# pic_board.net
KiCad netlist of a schematic drawn in EAGLE
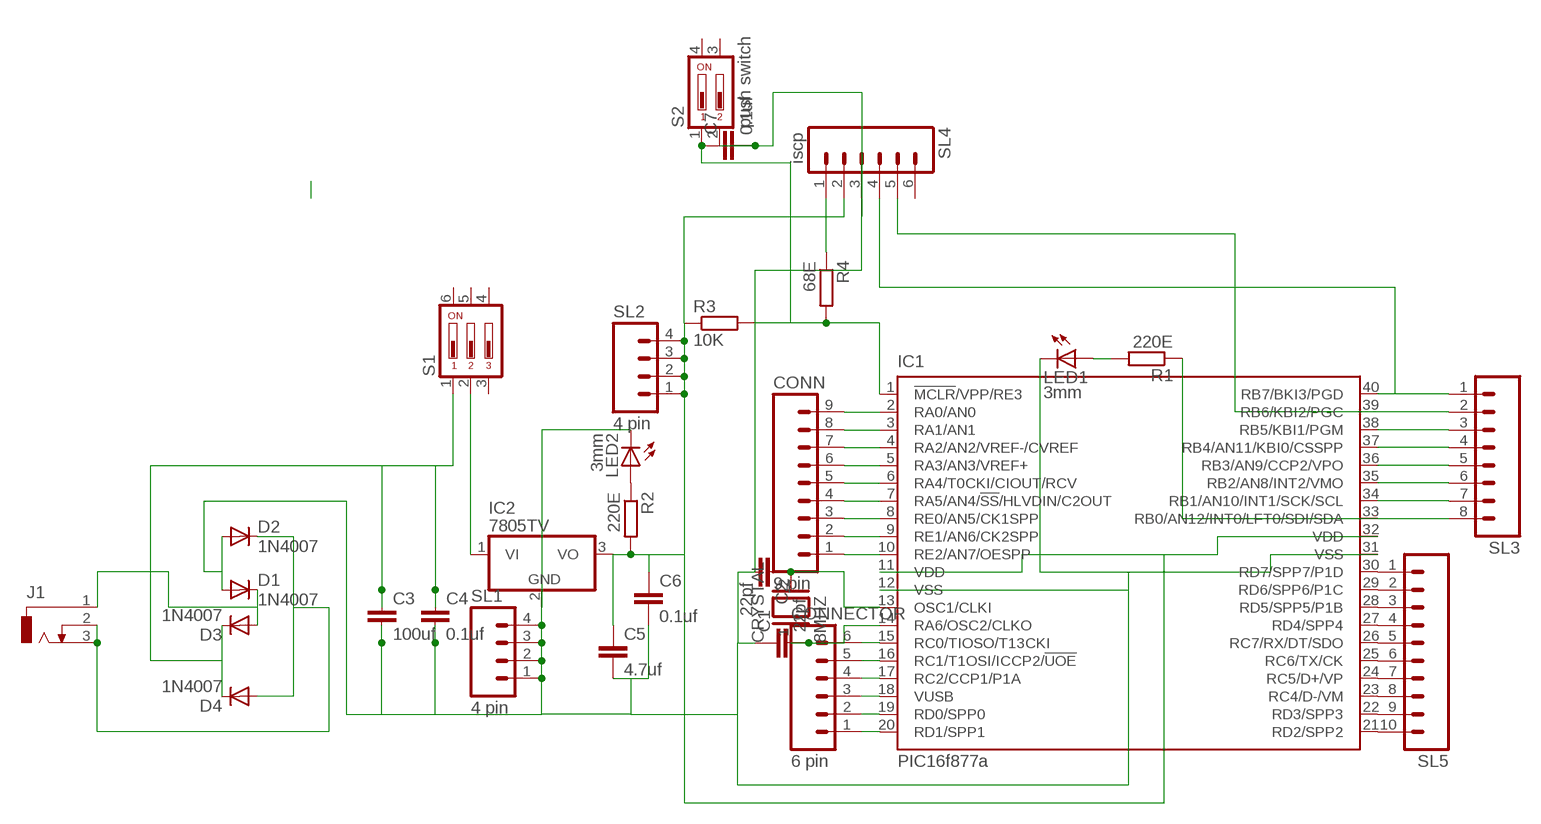
[diagram p0: schematic, sheet 1]

(export (version "E")
  (design (tool "Eeschema 10.0.6"))
  (components
    (comp (ref "C1")
      (value "22pf")
      (footprint "eagle-import:C2.5-2")
      (libsource (lib "eagle-import") (part "C2.5/2"))
    )
    (comp (ref "C2")
      (value "22pf")
      (footprint "eagle-import:C2.5-2")
      (libsource (lib "eagle-import") (part "C2.5/2"))
    )
    (comp (ref "C3")
      (value "100uf")
      (footprint "eagle-import:C5B7.2")
      (libsource (lib "eagle-import") (part "C5/7.2"))
    )
    (comp (ref "C4")
      (value "0.1uf")
      (footprint "eagle-import:C2.5-3")
      (libsource (lib "eagle-import") (part "C2,5-3"))
    )
    (comp (ref "C5")
      (value "4.7uf")
      (footprint "eagle-import:C5B7.2")
      (libsource (lib "eagle-import") (part "C5/7.2"))
    )
    (comp (ref "C6")
      (value "0.1uf")
      (footprint "eagle-import:C2.5-2")
      (libsource (lib "eagle-import") (part "C2.5/2"))
    )
    (comp (ref "C7")
      (value "0.1uf")
      (footprint "eagle-import:C2.5-3")
      (libsource (lib "eagle-import") (part "C2,5-3"))
    )
    (comp (ref "CONN")
      (value "9 pin")
      (footprint "eagle-import:09P")
      (libsource (lib "eagle-import") (part "M09"))
    )
    (comp (ref "CONNECTOR")
      (value "6 pin")
      (footprint "eagle-import:06P")
      (libsource (lib "eagle-import") (part "M06"))
    )
    (comp (ref "CRYSTAL")
      (value "8MHZ")
      (footprint "eagle-import:QS")
      (libsource (lib "eagle-import") (part "XTAL/S"))
    )
    (comp (ref "D1")
      (value "1N4007")
      (footprint "eagle-import:DO41-10")
      (libsource (lib "eagle-import") (part "1N4004"))
    )
    (comp (ref "D2")
      (value "1N4007")
      (footprint "eagle-import:DO41-10")
      (libsource (lib "eagle-import") (part "1N4004"))
    )
    (comp (ref "D3")
      (value "1N4007")
      (footprint "eagle-import:DO41-10")
      (libsource (lib "eagle-import") (part "1N4004"))
    )
    (comp (ref "D4")
      (value "1N4007")
      (footprint "eagle-import:DO41-10")
      (libsource (lib "eagle-import") (part "1N4004"))
    )
    (comp (ref "IC1")
      (value "PIC16f877a")
      (footprint "eagle-import:DIL40")
      (fields (field (name "MF") "MICROCHIP") (field (name "MPN") "PIC18F4455-I/P"))
      (libsource (lib "eagle-import") (part "PIC18F4_40455"))
    )
    (comp (ref "IC2")
      (value "7805TV")
      (footprint "eagle-import:TO220V")
      (libsource (lib "eagle-import") (part "78TV05"))
    )
    (comp (ref "J1")
      (value "DCJ0303")
      (footprint "eagle-import:DCJ0303")
      (libsource (lib "eagle-import") (part "DCJ0303"))
    )
    (comp (ref "LED1")
      (value "3mm")
      (footprint "eagle-import:LED3MM")
      (libsource (lib "eagle-import") (part "LED3MM"))
    )
    (comp (ref "LED2")
      (value "3mm")
      (footprint "eagle-import:LED3MM")
      (libsource (lib "eagle-import") (part "LED3MM"))
    )
    (comp (ref "R1")
      (value "220E")
      (footprint "eagle-import:0204_7")
      (libsource (lib "eagle-import") (part "R-EU_0204/7"))
    )
    (comp (ref "R2")
      (value "220E")
      (footprint "eagle-import:0204_7")
      (libsource (lib "eagle-import") (part "R-EU_0204/7"))
    )
    (comp (ref "R3")
      (value "10K")
      (footprint "eagle-import:0204_7")
      (libsource (lib "eagle-import") (part "R-EU_0204/7"))
    )
    (comp (ref "R4")
      (value "68E")
      (footprint "eagle-import:0204_7")
      (libsource (lib "eagle-import") (part "R-EU_0204/7"))
    )
    (comp (ref "S1")
      (value "DA03")
      (footprint "eagle-import:DA-03")
      (fields (field (name "MPN") "MCDA03"))
      (libsource (lib "eagle-import") (part "DA03"))
    )
    (comp (ref "S2")
      (value "push switch")
      (footprint "eagle-import:DP-02")
      (fields (field (name "MPN") "MCDP02"))
      (libsource (lib "eagle-import") (part "DP02"))
    )
    (comp (ref "SL1")
      (value "4 pin")
      (footprint "eagle-import:04P")
      (libsource (lib "eagle-import") (part "M04"))
    )
    (comp (ref "SL2")
      (value "4 pin")
      (footprint "eagle-import:04P")
      (libsource (lib "eagle-import") (part "M04"))
    )
    (comp (ref "SL3")
      (value "M08")
      (footprint "eagle-import:08P")
      (libsource (lib "eagle-import") (part "M08"))
    )
    (comp (ref "SL4")
      (value "iscp")
      (footprint "eagle-import:06P")
      (libsource (lib "eagle-import") (part "M06"))
    )
    (comp (ref "SL5")
      (value "M10")
      (footprint "eagle-import:10P")
      (libsource (lib "eagle-import") (part "M10"))
    )
  )
  (nets
    (net (code "1") (name "Net-(C3-Pad1)") (class "Default")
      (node (ref "C3") (pin "1") (pinfunction "1_1") (pintype "passive"))
      (node (ref "C4") (pin "1") (pinfunction "1_1") (pintype "passive"))
      (node (ref "D3") (pin "C") (pinfunction "C_C") (pintype "passive"))
      (node (ref "D4") (pin "C") (pinfunction "C_C") (pintype "passive"))
      (node (ref "S1") (pin "1") (pinfunction "1_1") (pintype "passive"))
    )
    (net (code "2") (name "Net-(D1-PadC)") (class "Default")
      (node (ref "D1") (pin "C") (pinfunction "C_C") (pintype "passive"))
      (node (ref "D3") (pin "A") (pinfunction "A_A") (pintype "passive"))
      (node (ref "J1") (pin "1") (pinfunction "1_1") (pintype "passive"))
    )
    (net (code "3") (name "Net-(D2-PadC)") (class "Default")
      (node (ref "D2") (pin "C") (pinfunction "C_C") (pintype "passive"))
      (node (ref "D4") (pin "A") (pinfunction "A_A") (pintype "passive"))
      (node (ref "J1") (pin "2") (pinfunction "2_2") (pintype "passive"))
      (node (ref "J1") (pin "3") (pinfunction "3_3") (pintype "passive"))
    )
    (net (code "4") (name "Net-(IC1-OSC1{slash}CLKI)") (class "Default")
      (node (ref "C2") (pin "1") (pinfunction "1_1") (pintype "passive"))
      (node (ref "CRYSTAL") (pin "2") (pinfunction "2_2") (pintype "passive"))
      (node (ref "IC1") (pin "13") (pinfunction "OSC1/CLKI_13") (pintype "input"))
    )
    (net (code "5") (name "Net-(IC1-RA0{slash}AN0)") (class "Default")
      (node (ref "CONN") (pin "9") (pinfunction "9_9") (pintype "passive"))
      (node (ref "IC1") (pin "2") (pinfunction "RA0/AN0_2") (pintype "bidirectional"))
    )
    (net (code "6") (name "Net-(IC1-RA1{slash}AN1)") (class "Default")
      (node (ref "CONN") (pin "8") (pinfunction "8_8") (pintype "passive"))
      (node (ref "IC1") (pin "3") (pinfunction "RA1/AN1_3") (pintype "bidirectional"))
    )
    (net (code "7") (name "Net-(IC1-RA2{slash}AN2{slash}VREF-{slash}CVREF)") (class "Default")
      (node (ref "CONN") (pin "7") (pinfunction "7_7") (pintype "passive"))
      (node (ref "IC1") (pin "4") (pinfunction "RA2/AN2/VREF-/CVREF_4") (pintype "bidirectional"))
    )
    (net (code "8") (name "Net-(IC1-RA3{slash}AN3{slash}VREF+)") (class "Default")
      (node (ref "CONN") (pin "6") (pinfunction "6_6") (pintype "passive"))
      (node (ref "IC1") (pin "5") (pinfunction "RA3/AN3/VREF+_5") (pintype "bidirectional"))
    )
    (net (code "9") (name "Net-(IC1-RA4{slash}T0CKI{slash}CIOUT{slash}RCV)") (class "Default")
      (node (ref "CONN") (pin "5") (pinfunction "5_5") (pintype "passive"))
      (node (ref "IC1") (pin "6") (pinfunction "RA4/T0CKI/CIOUT/RCV_6") (pintype "bidirectional"))
    )
    (net (code "10") (name "Net-(IC1-RA5{slash}AN4{slash}~{SS}{slash}HLVDIN{slash}C2OUT)") (class "Default")
      (node (ref "CONN") (pin "4") (pinfunction "4_4") (pintype "passive"))
      (node (ref "IC1") (pin "7") (pinfunction "RA5/AN4/~{SS}/HLVDIN/C2OUT_7") (pintype "bidirectional"))
    )
    (net (code "11") (name "Net-(IC1-RA6{slash}OSC2{slash}CLKO)") (class "Default")
      (node (ref "C1") (pin "2") (pinfunction "2_2") (pintype "passive"))
      (node (ref "CRYSTAL") (pin "1") (pinfunction "1_1") (pintype "passive"))
      (node (ref "IC1") (pin "14") (pinfunction "RA6/OSC2/CLKO_14") (pintype "output"))
    )
    (net (code "12") (name "Net-(IC1-RB0{slash}AN12{slash}INT0{slash}LFT0{slash}SDI{slash}SDA)") (class "Default")
      (node (ref "IC1") (pin "33") (pinfunction "RB0/AN12/INT0/LFT0/SDI/SDA_33") (pintype "bidirectional"))
      (node (ref "R1") (pin "1") (pinfunction "1_1") (pintype "passive"))
      (node (ref "SL3") (pin "8") (pinfunction "8_8") (pintype "passive"))
    )
    (net (code "13") (name "Net-(IC1-RB1{slash}AN10{slash}INT1{slash}SCK{slash}SCL)") (class "Default")
      (node (ref "IC1") (pin "34") (pinfunction "RB1/AN10/INT1/SCK/SCL_34") (pintype "bidirectional"))
      (node (ref "SL3") (pin "7") (pinfunction "7_7") (pintype "passive"))
    )
    (net (code "14") (name "Net-(IC1-RB2{slash}AN8{slash}INT2{slash}VMO)") (class "Default")
      (node (ref "IC1") (pin "35") (pinfunction "RB2/AN8/INT2/VMO_35") (pintype "bidirectional"))
      (node (ref "SL3") (pin "6") (pinfunction "6_6") (pintype "passive"))
    )
    (net (code "15") (name "Net-(IC1-RB3{slash}AN9{slash}CCP2{slash}VPO)") (class "Default")
      (node (ref "IC1") (pin "36") (pinfunction "RB3/AN9/CCP2/VPO_36") (pintype "bidirectional"))
      (node (ref "SL3") (pin "5") (pinfunction "5_5") (pintype "passive"))
    )
    (net (code "16") (name "Net-(IC1-RB4{slash}AN11{slash}KBI0{slash}CSSPP)") (class "Default")
      (node (ref "IC1") (pin "37") (pinfunction "RB4/AN11/KBI0/CSSPP_37") (pintype "bidirectional"))
      (node (ref "SL3") (pin "4") (pinfunction "4_4") (pintype "passive"))
    )
    (net (code "17") (name "Net-(IC1-RB5{slash}KBI1{slash}PGM)") (class "Default")
      (node (ref "IC1") (pin "38") (pinfunction "RB5/KBI1/PGM_38") (pintype "bidirectional"))
      (node (ref "SL3") (pin "3") (pinfunction "3_3") (pintype "passive"))
    )
    (net (code "18") (name "Net-(IC1-RB6{slash}KBI2{slash}PGC)") (class "Default")
      (node (ref "IC1") (pin "39") (pinfunction "RB6/KBI2/PGC_39") (pintype "bidirectional"))
      (node (ref "SL3") (pin "2") (pinfunction "2_2") (pintype "passive"))
      (node (ref "SL4") (pin "5") (pinfunction "5_5") (pintype "passive"))
    )
    (net (code "19") (name "Net-(IC1-RB7{slash}BKI3{slash}PGD)") (class "Default")
      (node (ref "IC1") (pin "40") (pinfunction "RB7/BKI3/PGD_40") (pintype "bidirectional"))
      (node (ref "SL3") (pin "1") (pinfunction "1_1") (pintype "passive"))
      (node (ref "SL4") (pin "4") (pinfunction "4_4") (pintype "passive"))
    )
    (net (code "20") (name "Net-(IC1-RC0{slash}TIOSO{slash}T13CKI)") (class "Default")
      (node (ref "CONNECTOR") (pin "6") (pinfunction "6_6") (pintype "passive"))
      (node (ref "IC1") (pin "15") (pinfunction "RC0/TIOSO/T13CKI_15") (pintype "bidirectional"))
    )
    (net (code "21") (name "Net-(IC1-RC1{slash}T1OSI{slash}ICCP2{slash}~{UOE})") (class "Default")
      (node (ref "CONNECTOR") (pin "5") (pinfunction "5_5") (pintype "passive"))
      (node (ref "IC1") (pin "16") (pinfunction "RC1/T1OSI/ICCP2/~{UOE}_16") (pintype "bidirectional"))
    )
    (net (code "22") (name "Net-(IC1-RC2{slash}CCP1{slash}P1A)") (class "Default")
      (node (ref "CONNECTOR") (pin "4") (pinfunction "4_4") (pintype "passive"))
      (node (ref "IC1") (pin "17") (pinfunction "RC2/CCP1/P1A_17") (pintype "bidirectional"))
    )
    (net (code "23") (name "Net-(IC1-RC4{slash}D-{slash}VM)") (class "Default")
      (node (ref "IC1") (pin "23") (pinfunction "RC4/D-/VM_23") (pintype "bidirectional"))
      (node (ref "SL5") (pin "8") (pinfunction "8_8") (pintype "passive"))
    )
    (net (code "24") (name "Net-(IC1-RC5{slash}D+{slash}VP)") (class "Default")
      (node (ref "IC1") (pin "24") (pinfunction "RC5/D+/VP_24") (pintype "bidirectional"))
      (node (ref "SL5") (pin "7") (pinfunction "7_7") (pintype "passive"))
    )
    (net (code "25") (name "Net-(IC1-RC6{slash}TX{slash}CK)") (class "Default")
      (node (ref "IC1") (pin "25") (pinfunction "RC6/TX/CK_25") (pintype "bidirectional"))
      (node (ref "SL5") (pin "6") (pinfunction "6_6") (pintype "passive"))
    )
    (net (code "26") (name "Net-(IC1-RC7{slash}RX{slash}DT{slash}SDO)") (class "Default")
      (node (ref "IC1") (pin "26") (pinfunction "RC7/RX/DT/SDO_26") (pintype "bidirectional"))
      (node (ref "SL5") (pin "5") (pinfunction "5_5") (pintype "passive"))
    )
    (net (code "27") (name "Net-(IC1-RD0{slash}SPP0)") (class "Default")
      (node (ref "CONNECTOR") (pin "2") (pinfunction "2_2") (pintype "passive"))
      (node (ref "IC1") (pin "19") (pinfunction "RD0/SPP0_19") (pintype "bidirectional"))
    )
    (net (code "28") (name "Net-(IC1-RD1{slash}SPP1)") (class "Default")
      (node (ref "CONNECTOR") (pin "1") (pinfunction "1_1") (pintype "passive"))
      (node (ref "IC1") (pin "20") (pinfunction "RD1/SPP1_20") (pintype "bidirectional"))
    )
    (net (code "29") (name "Net-(IC1-RD2{slash}SPP2)") (class "Default")
      (node (ref "IC1") (pin "21") (pinfunction "RD2/SPP2_21") (pintype "bidirectional"))
      (node (ref "SL5") (pin "10") (pinfunction "10_10") (pintype "passive"))
    )
    (net (code "30") (name "Net-(IC1-RD3{slash}SPP3)") (class "Default")
      (node (ref "IC1") (pin "22") (pinfunction "RD3/SPP3_22") (pintype "bidirectional"))
      (node (ref "SL5") (pin "9") (pinfunction "9_9") (pintype "passive"))
    )
    (net (code "31") (name "Net-(IC1-RD4{slash}SPP4)") (class "Default")
      (node (ref "IC1") (pin "27") (pinfunction "RD4/SPP4_27") (pintype "bidirectional"))
      (node (ref "SL5") (pin "4") (pinfunction "4_4") (pintype "passive"))
    )
    (net (code "32") (name "Net-(IC1-RD5{slash}SPP5{slash}P1B)") (class "Default")
      (node (ref "IC1") (pin "28") (pinfunction "RD5/SPP5/P1B_28") (pintype "bidirectional"))
      (node (ref "SL5") (pin "3") (pinfunction "3_3") (pintype "passive"))
    )
    (net (code "33") (name "Net-(IC1-RD6{slash}SPP6{slash}P1C)") (class "Default")
      (node (ref "IC1") (pin "29") (pinfunction "RD6/SPP6/P1C_29") (pintype "bidirectional"))
      (node (ref "SL5") (pin "2") (pinfunction "2_2") (pintype "passive"))
    )
    (net (code "34") (name "Net-(IC1-RD7{slash}SPP7{slash}P1D)") (class "Default")
      (node (ref "IC1") (pin "30") (pinfunction "RD7/SPP7/P1D_30") (pintype "bidirectional"))
      (node (ref "SL5") (pin "1") (pinfunction "1_1") (pintype "passive"))
    )
    (net (code "35") (name "Net-(IC1-RE0{slash}AN5{slash}CK1SPP)") (class "Default")
      (node (ref "CONN") (pin "3") (pinfunction "3_3") (pintype "passive"))
      (node (ref "IC1") (pin "8") (pinfunction "RE0/AN5/CK1SPP_8") (pintype "bidirectional"))
    )
    (net (code "36") (name "Net-(IC1-RE1{slash}AN6{slash}CK2SPP)") (class "Default")
      (node (ref "CONN") (pin "2") (pinfunction "2_2") (pintype "passive"))
      (node (ref "IC1") (pin "9") (pinfunction "RE1/AN6/CK2SPP_9") (pintype "bidirectional"))
    )
    (net (code "37") (name "Net-(IC1-RE2{slash}AN7{slash}OESPP)") (class "Default")
      (node (ref "CONN") (pin "1") (pinfunction "1_1") (pintype "passive"))
      (node (ref "IC1") (pin "10") (pinfunction "RE2/AN7/OESPP_10") (pintype "bidirectional"))
    )
    (net (code "38") (name "Net-(IC1-VUSB)") (class "Default")
      (node (ref "CONNECTOR") (pin "3") (pinfunction "3_3") (pintype "passive"))
      (node (ref "IC1") (pin "18") (pinfunction "VUSB_18") (pintype "bidirectional"))
    )
    (net (code "39") (name "Net-(IC1-~{MCLR}{slash}VPP{slash}RE3)") (class "Default")
      (node (ref "C7") (pin "1") (pinfunction "1_1") (pintype "passive"))
      (node (ref "IC1") (pin "1") (pinfunction "~{MCLR}/VPP/RE3_1") (pintype "input"))
      (node (ref "R3") (pin "2") (pinfunction "2_2") (pintype "passive"))
      (node (ref "R4") (pin "2") (pinfunction "2_2") (pintype "passive"))
      (node (ref "S2") (pin "1") (pinfunction "1_1") (pintype "passive"))
    )
    (net (code "40") (name "Net-(IC2-GND)") (class "Default")
      (node (ref "C1") (pin "1") (pinfunction "1_1") (pintype "passive"))
      (node (ref "C2") (pin "2") (pinfunction "2_2") (pintype "passive"))
      (node (ref "C3") (pin "2") (pinfunction "2_2") (pintype "passive"))
      (node (ref "C4") (pin "2") (pinfunction "2_2") (pintype "passive"))
      (node (ref "C5") (pin "2") (pinfunction "2_2") (pintype "passive"))
      (node (ref "C6") (pin "2") (pinfunction "2_2") (pintype "passive"))
      (node (ref "C7") (pin "2") (pinfunction "2_2") (pintype "passive"))
      (node (ref "D1") (pin "A") (pinfunction "A_A") (pintype "passive"))
      (node (ref "D2") (pin "A") (pinfunction "A_A") (pintype "passive"))
      (node (ref "IC1") (pin "12") (pinfunction "VSS_12") (pintype "power_in"))
      (node (ref "IC1") (pin "31") (pinfunction "VSS_31") (pintype "power_in"))
      (node (ref "IC2") (pin "2") (pinfunction "GND_2") (pintype "passive"))
      (node (ref "LED1") (pin "K") (pinfunction "C_K") (pintype "passive"))
      (node (ref "LED2") (pin "K") (pinfunction "C_K") (pintype "passive"))
      (node (ref "S2") (pin "2") (pinfunction "2_2") (pintype "passive"))
      (node (ref "SL1") (pin "1") (pinfunction "1_1") (pintype "passive"))
      (node (ref "SL1") (pin "2") (pinfunction "2_2") (pintype "passive"))
      (node (ref "SL1") (pin "3") (pinfunction "3_3") (pintype "passive"))
      (node (ref "SL1") (pin "4") (pinfunction "4_4") (pintype "passive"))
      (node (ref "SL4") (pin "3") (pinfunction "3_3") (pintype "passive"))
    )
    (net (code "41") (name "Net-(IC2-VI)") (class "Default")
      (node (ref "IC2") (pin "1") (pinfunction "VI_1") (pintype "input"))
      (node (ref "S1") (pin "2") (pinfunction "2_2") (pintype "passive"))
    )
    (net (code "42") (name "Net-(IC2-VO)") (class "Default")
      (node (ref "C5") (pin "1") (pinfunction "1_1") (pintype "passive"))
      (node (ref "C6") (pin "1") (pinfunction "1_1") (pintype "passive"))
      (node (ref "IC1") (pin "11") (pinfunction "VDD_11") (pintype "power_in"))
      (node (ref "IC1") (pin "32") (pinfunction "VDD_32") (pintype "power_in"))
      (node (ref "IC2") (pin "3") (pinfunction "VO_3") (pintype "passive"))
      (node (ref "R2") (pin "2") (pinfunction "2_2") (pintype "passive"))
      (node (ref "R3") (pin "1") (pinfunction "1_1") (pintype "passive"))
      (node (ref "SL2") (pin "1") (pinfunction "1_1") (pintype "passive"))
      (node (ref "SL2") (pin "2") (pinfunction "2_2") (pintype "passive"))
      (node (ref "SL2") (pin "3") (pinfunction "3_3") (pintype "passive"))
      (node (ref "SL2") (pin "4") (pinfunction "4_4") (pintype "passive"))
      (node (ref "SL4") (pin "2") (pinfunction "2_2") (pintype "passive"))
    )
    (net (code "43") (name "Net-(LED1-PadA)") (class "Default")
      (node (ref "LED1") (pin "A") (pinfunction "A_A") (pintype "passive"))
      (node (ref "R1") (pin "2") (pinfunction "2_2") (pintype "passive"))
    )
    (net (code "44") (name "Net-(LED2-PadA)") (class "Default")
      (node (ref "LED2") (pin "A") (pinfunction "A_A") (pintype "passive"))
      (node (ref "R2") (pin "1") (pinfunction "1_1") (pintype "passive"))
    )
    (net (code "45") (name "Net-(R4-Pad1)") (class "Default")
      (node (ref "R4") (pin "1") (pinfunction "1_1") (pintype "passive"))
      (node (ref "SL4") (pin "1") (pinfunction "1_1") (pintype "passive"))
    )
    (net (code "46") (name "unconnected-(S1-Pad3)") (class "Default")
      (node (ref "S1") (pin "3") (pinfunction "3_3") (pintype "passive"))
    )
    (net (code "47") (name "unconnected-(S1-Pad4)") (class "Default")
      (node (ref "S1") (pin "4") (pinfunction "4_4") (pintype "passive"))
    )
    (net (code "48") (name "unconnected-(S1-Pad5)") (class "Default")
      (node (ref "S1") (pin "5") (pinfunction "5_5") (pintype "passive"))
    )
    (net (code "49") (name "unconnected-(S1-Pad6)") (class "Default")
      (node (ref "S1") (pin "6") (pinfunction "6_6") (pintype "passive"))
    )
    (net (code "50") (name "unconnected-(S2-Pad3)") (class "Default")
      (node (ref "S2") (pin "3") (pinfunction "3_3") (pintype "passive"))
    )
    (net (code "51") (name "unconnected-(S2-Pad4)") (class "Default")
      (node (ref "S2") (pin "4") (pinfunction "4_4") (pintype "passive"))
    )
    (net (code "52") (name "unconnected-(SL4-Pad6)") (class "Default")
      (node (ref "SL4") (pin "6") (pinfunction "6_6") (pintype "passive"))
    )
  )
)
